# Sheet_1.net
KiCad netlist of a schematic drawn in Altium Designer
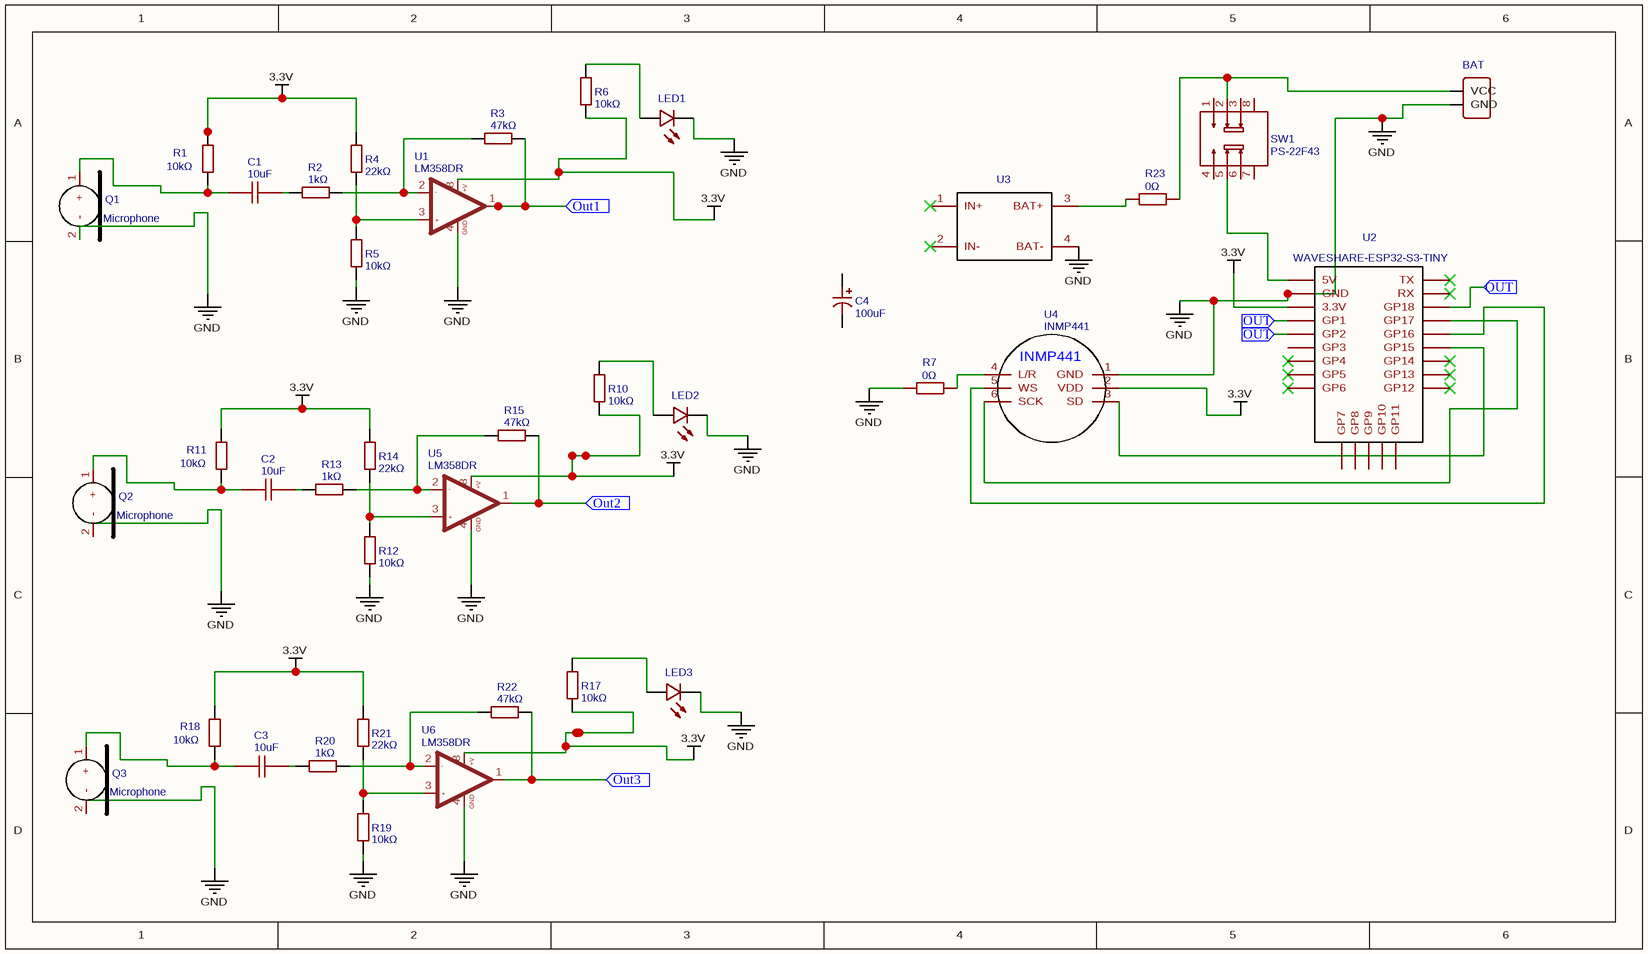
[diagram p0: Sheet_1_.schdoc]

(export (version "E")
  (design (tool "Eeschema 10.0.6"))
  (components
    (comp (ref "BAT")
      (value "HDR-F-2.54_1x2")
      (fields (field (name "CONTRIBUTOR") "LCEDA_Lib"))
      (libsource (lib "altium-import") (part "root_0_HDR-F-2.54_1x2_"))
    )
    (comp (ref "C1")
      (value "10uF")
      (fields
        (field (name "MANUFACTURER PART") "CL21A106KAYNNNE")
        (field (name "MANUFACTURER") "SAMSUNG(三星)")
      )
      (libsource (lib "altium-import") (part "root_0_10uF_"))
    )
    (comp (ref "C2")
      (value "10uF")
      (fields
        (field (name "MANUFACTURER PART") "CL21A106KAYNNNE")
        (field (name "MANUFACTURER") "SAMSUNG(三星)")
      )
      (libsource (lib "altium-import") (part "root_0_10uF_"))
    )
    (comp (ref "C3")
      (value "10uF")
      (fields
        (field (name "MANUFACTURER PART") "CL21A106KAYNNNE")
        (field (name "MANUFACTURER") "SAMSUNG(三星)")
      )
      (libsource (lib "altium-import") (part "root_0_10uF_"))
    )
    (comp (ref "C4")
      (value "100uF")
      (fields
        (field (name "MANUFACTURER") "KNSCHA(科尼盛)")
        (field (name "MANUFACTURER PART") "RVT100UF16V67RV0016")
        (field (name "CONTRIBUTOR") "LCSC")
      )
      (libsource (lib "altium-import") (part "root_3_100uF_"))
    )
    (comp (ref "LED1")
      (value "19-217/BHC-ZL1M2RY/3T")
      (fields (field (name "MANUFACTURER") "EVERLIGHT(亿光)"))
      (libsource (lib "altium-import") (part "root_2_19-217/BHC-ZL1M2RY/3T_"))
    )
    (comp (ref "LED2")
      (value "19-217/BHC-ZL1M2RY/3T")
      (fields (field (name "MANUFACTURER") "EVERLIGHT(亿光)"))
      (libsource (lib "altium-import") (part "root_2_19-217/BHC-ZL1M2RY/3T_"))
    )
    (comp (ref "LED3")
      (value "19-217/BHC-ZL1M2RY/3T")
      (fields (field (name "MANUFACTURER") "EVERLIGHT(亿光)"))
      (libsource (lib "altium-import") (part "root_2_19-217/BHC-ZL1M2RY/3T_"))
    )
    (comp (ref "Q1")
      (value "Microphone")
      (fields (field (name "CONTRIBUTOR") "Мастерская Ленара"))
      (libsource (lib "altium-import") (part "root_0_Microphone_"))
    )
    (comp (ref "Q2")
      (value "Microphone")
      (fields (field (name "CONTRIBUTOR") "Мастерская Ленара"))
      (libsource (lib "altium-import") (part "root_0_Microphone_"))
    )
    (comp (ref "Q3")
      (value "Microphone")
      (fields (field (name "CONTRIBUTOR") "Мастерская Ленара"))
      (libsource (lib "altium-import") (part "root_0_Microphone_"))
    )
    (comp (ref "R1")
      (value "10kΩ")
      (fields (field (name "MANUFACTURER") "YAGEO(国巨)") (field (name "MANUFACTURER PART") "RC0402FR-0710KL"))
      (libsource (lib "altium-import") (part "root_1_10kΩ_"))
    )
    (comp (ref "R2")
      (value "1kΩ")
      (fields
        (field (name "MANUFACTURER") "UNI-ROYAL(厚声)")
        (field (name "MANUFACTURER PART") "0402WGF1001TCE")
      )
      (libsource (lib "altium-import") (part "root_0_1kΩ_"))
    )
    (comp (ref "R3")
      (value "47kΩ")
      (fields
        (field (name "MANUFACTURER") "UNI-ROYAL(厚声)")
        (field (name "MANUFACTURER PART") "0402WGF4702TCE")
      )
      (libsource (lib "altium-import") (part "root_0_47kΩ_"))
    )
    (comp (ref "R4")
      (value "22kΩ")
      (fields
        (field (name "MANUFACTURER") "UNI-ROYAL(厚声)")
        (field (name "MANUFACTURER PART") "0402WGF2202TCE")
      )
      (libsource (lib "altium-import") (part "root_1_22kΩ_"))
    )
    (comp (ref "R5")
      (value "10kΩ")
      (fields (field (name "MANUFACTURER") "YAGEO(国巨)") (field (name "MANUFACTURER PART") "RC0402FR-0710KL"))
      (libsource (lib "altium-import") (part "root_1_10kΩ_"))
    )
    (comp (ref "R6")
      (value "10kΩ")
      (fields (field (name "MANUFACTURER") "YAGEO(国巨)") (field (name "MANUFACTURER PART") "RC0402FR-0710KL"))
      (libsource (lib "altium-import") (part "root_1_10kΩ_"))
    )
    (comp (ref "R7")
      (value "0Ω")
      (fields
        (field (name "MANUFACTURER") "UNI-ROYAL(厚声)")
        (field (name "MANUFACTURER PART") "201007F0000T4E")
        (field (name "CONTRIBUTOR") "LCSC")
      )
      (libsource (lib "altium-import") (part "root_0_0Ω_"))
    )
    (comp (ref "R10")
      (value "10kΩ")
      (fields (field (name "MANUFACTURER") "YAGEO(国巨)") (field (name "MANUFACTURER PART") "RC0402FR-0710KL"))
      (libsource (lib "altium-import") (part "root_1_10kΩ_"))
    )
    (comp (ref "R11")
      (value "10kΩ")
      (fields (field (name "MANUFACTURER") "YAGEO(国巨)") (field (name "MANUFACTURER PART") "RC0402FR-0710KL"))
      (libsource (lib "altium-import") (part "root_1_10kΩ_"))
    )
    (comp (ref "R12")
      (value "10kΩ")
      (fields (field (name "MANUFACTURER") "YAGEO(国巨)") (field (name "MANUFACTURER PART") "RC0402FR-0710KL"))
      (libsource (lib "altium-import") (part "root_1_10kΩ_"))
    )
    (comp (ref "R13")
      (value "1kΩ")
      (fields
        (field (name "MANUFACTURER") "UNI-ROYAL(厚声)")
        (field (name "MANUFACTURER PART") "0402WGF1001TCE")
      )
      (libsource (lib "altium-import") (part "root_0_1kΩ_"))
    )
    (comp (ref "R14")
      (value "22kΩ")
      (fields
        (field (name "MANUFACTURER") "UNI-ROYAL(厚声)")
        (field (name "MANUFACTURER PART") "0402WGF2202TCE")
      )
      (libsource (lib "altium-import") (part "root_1_22kΩ_"))
    )
    (comp (ref "R15")
      (value "47kΩ")
      (fields
        (field (name "MANUFACTURER") "UNI-ROYAL(厚声)")
        (field (name "MANUFACTURER PART") "0402WGF4702TCE")
      )
      (libsource (lib "altium-import") (part "root_0_47kΩ_"))
    )
    (comp (ref "R17")
      (value "10kΩ")
      (fields (field (name "MANUFACTURER") "YAGEO(国巨)") (field (name "MANUFACTURER PART") "RC0402FR-0710KL"))
      (libsource (lib "altium-import") (part "root_1_10kΩ_"))
    )
    (comp (ref "R18")
      (value "10kΩ")
      (fields (field (name "MANUFACTURER") "YAGEO(国巨)") (field (name "MANUFACTURER PART") "RC0402FR-0710KL"))
      (libsource (lib "altium-import") (part "root_1_10kΩ_"))
    )
    (comp (ref "R19")
      (value "10kΩ")
      (fields (field (name "MANUFACTURER") "YAGEO(国巨)") (field (name "MANUFACTURER PART") "RC0402FR-0710KL"))
      (libsource (lib "altium-import") (part "root_1_10kΩ_"))
    )
    (comp (ref "R20")
      (value "1kΩ")
      (fields
        (field (name "MANUFACTURER") "UNI-ROYAL(厚声)")
        (field (name "MANUFACTURER PART") "0402WGF1001TCE")
      )
      (libsource (lib "altium-import") (part "root_0_1kΩ_"))
    )
    (comp (ref "R21")
      (value "22kΩ")
      (fields
        (field (name "MANUFACTURER") "UNI-ROYAL(厚声)")
        (field (name "MANUFACTURER PART") "0402WGF2202TCE")
      )
      (libsource (lib "altium-import") (part "root_1_22kΩ_"))
    )
    (comp (ref "R22")
      (value "47kΩ")
      (fields
        (field (name "MANUFACTURER") "UNI-ROYAL(厚声)")
        (field (name "MANUFACTURER PART") "0402WGF4702TCE")
      )
      (libsource (lib "altium-import") (part "root_0_47kΩ_"))
    )
    (comp (ref "R23")
      (value "0Ω")
      (fields
        (field (name "MANUFACTURER") "UNI-ROYAL(厚声)")
        (field (name "MANUFACTURER PART") "201007F0000T4E")
        (field (name "CONTRIBUTOR") "LCSC")
      )
      (libsource (lib "altium-import") (part "root_0_0Ω_"))
    )
    (comp (ref "SW1")
      (value "PS-22F43")
      (fields (field (name "MANUFACTURER") "G-Switch(品赞)") (field (name "CONTRIBUTOR") "lcsc"))
      (libsource (lib "altium-import") (part "root_0_PS-22F43_"))
    )
    (comp (ref "U1")
      (value "LM358DR")
      (fields (field (name "SUBPART_NO") "1") (field (name "MANUFACTURER") "TI(德州仪器)"))
      (libsource (lib "altium-import") (part "root_0_LM358DR_"))
    )
    (comp (ref "U2")
      (value "WAVESHARE-ESP32-S3-TINY")
      (fields
        (field (name "MANUFACTURER") "WAVESHARE")
        (field (name "MANUFACTURER PART") "ESP32-S3 Mini Development Board")
        (field (name "CONTRIBUTOR") "Mohammed Jerjawi")
      )
      (libsource (lib "altium-import") (part "root_0_WAVESHARE-ESP32-S3-TINY_"))
    )
    (comp (ref "U3")
      (value "Battery Protection  tp4056")
      (fields (field (name "CONTRIBUTOR") "gxgx"))
      (libsource (lib "altium-import") (part "root_0_Battery Protection  tp4056_"))
    )
    (comp (ref "U4")
      (value "INMP441")
      (fields (field (name "MANUFACTURER") "Ali") (field (name "CONTRIBUTOR") "Guest"))
      (libsource (lib "altium-import") (part "root_0_INMP441_"))
    )
    (comp (ref "U5")
      (value "LM358DR")
      (fields (field (name "SUBPART_NO") "1") (field (name "MANUFACTURER") "TI(德州仪器)"))
      (libsource (lib "altium-import") (part "root_0_LM358DR_"))
    )
    (comp (ref "U6")
      (value "LM358DR")
      (fields (field (name "SUBPART_NO") "1") (field (name "MANUFACTURER") "TI(德州仪器)"))
      (libsource (lib "altium-import") (part "root_0_LM358DR_"))
    )
  )
  (nets
    (net (code "1") (name "/OUT") (class "Default")
      (node (ref "U2") (pin "21") (pinfunction "GP18_21") (pintype "passive"))
      (node (ref "U2") (pin "4") (pinfunction "GP1_4") (pintype "passive"))
      (node (ref "U2") (pin "5") (pinfunction "GP2_5") (pintype "passive"))
    )
    (net (code "2") (name "/Out1") (class "Default")
      (node (ref "R3") (pin "2") (pinfunction "2_2") (pintype "passive"))
      (node (ref "U1") (pin "1") (pinfunction "OUT1_1") (pintype "passive"))
    )
    (net (code "3") (name "/Out2") (class "Default")
      (node (ref "R15") (pin "2") (pinfunction "2_2") (pintype "passive"))
      (node (ref "U5") (pin "1") (pinfunction "OUT1_1") (pintype "passive"))
    )
    (net (code "4") (name "/Out3") (class "Default")
      (node (ref "R22") (pin "2") (pinfunction "2_2") (pintype "passive"))
      (node (ref "U6") (pin "1") (pinfunction "OUT1_1") (pintype "passive"))
    )
    (net (code "5") (name "3.3V") (class "Default")
      (node (ref "R1") (pin "2") (pinfunction "2_2") (pintype "passive"))
      (node (ref "R10") (pin "1") (pinfunction "1_1") (pintype "passive"))
      (node (ref "R11") (pin "2") (pinfunction "2_2") (pintype "passive"))
      (node (ref "R14") (pin "2") (pinfunction "2_2") (pintype "passive"))
      (node (ref "R17") (pin "1") (pinfunction "1_1") (pintype "passive"))
      (node (ref "R18") (pin "2") (pinfunction "2_2") (pintype "passive"))
      (node (ref "R21") (pin "2") (pinfunction "2_2") (pintype "passive"))
      (node (ref "R4") (pin "2") (pinfunction "2_2") (pintype "passive"))
      (node (ref "R6") (pin "1") (pinfunction "1_1") (pintype "passive"))
      (node (ref "U1") (pin "8") (pinfunction "+V_8") (pintype "passive"))
      (node (ref "U2") (pin "3") (pinfunction "3.3V_3") (pintype "passive"))
      (node (ref "U4") (pin "2") (pinfunction "VDD_2") (pintype "passive"))
      (node (ref "U5") (pin "8") (pinfunction "+V_8") (pintype "passive"))
      (node (ref "U6") (pin "8") (pinfunction "+V_8") (pintype "passive"))
    )
    (net (code "6") (name "GND") (class "Default")
      (node (ref "BAT") (pin "2") (pinfunction "GND_2") (pintype "passive"))
      (node (ref "LED1") (pin "1") (pinfunction "C_1") (pintype "passive"))
      (node (ref "LED2") (pin "1") (pinfunction "C_1") (pintype "passive"))
      (node (ref "LED3") (pin "1") (pinfunction "C_1") (pintype "passive"))
      (node (ref "Q1") (pin "2") (pinfunction "-_2") (pintype "passive"))
      (node (ref "Q2") (pin "2") (pinfunction "-_2") (pintype "passive"))
      (node (ref "Q3") (pin "2") (pinfunction "-_2") (pintype "passive"))
      (node (ref "R12") (pin "1") (pinfunction "1_1") (pintype "passive"))
      (node (ref "R19") (pin "1") (pinfunction "1_1") (pintype "passive"))
      (node (ref "R5") (pin "1") (pinfunction "1_1") (pintype "passive"))
      (node (ref "R7") (pin "1") (pinfunction "1_1") (pintype "passive"))
      (node (ref "U1") (pin "4") (pinfunction "GND_4") (pintype "passive"))
      (node (ref "U2") (pin "2") (pinfunction "GND_2") (pintype "passive"))
      (node (ref "U3") (pin "4") (pinfunction "BAT-_4") (pintype "passive"))
      (node (ref "U4") (pin "1") (pinfunction "GND_1") (pintype "passive"))
      (node (ref "U5") (pin "4") (pinfunction "GND_4") (pintype "passive"))
      (node (ref "U6") (pin "4") (pinfunction "GND_4") (pintype "passive"))
    )
    (net (code "7") (name "Net-(BAT-VCC)") (class "Default")
      (node (ref "BAT") (pin "1") (pinfunction "VCC_1") (pintype "passive"))
      (node (ref "R23") (pin "2") (pinfunction "2_2") (pintype "passive"))
      (node (ref "SW1") (pin "2") (pinfunction "2_2") (pintype "passive"))
    )
    (net (code "8") (name "Net-(C1-Pad2)") (class "Default")
      (node (ref "C1") (pin "2") (pinfunction "2_2") (pintype "passive"))
      (node (ref "R2") (pin "1") (pinfunction "1_1") (pintype "passive"))
    )
    (net (code "9") (name "Net-(C2-Pad2)") (class "Default")
      (node (ref "C2") (pin "2") (pinfunction "2_2") (pintype "passive"))
      (node (ref "R13") (pin "1") (pinfunction "1_1") (pintype "passive"))
    )
    (net (code "10") (name "Net-(C3-Pad2)") (class "Default")
      (node (ref "C3") (pin "2") (pinfunction "2_2") (pintype "passive"))
      (node (ref "R20") (pin "1") (pinfunction "1_1") (pintype "passive"))
    )
    (net (code "11") (name "Net-(LED1-A)") (class "Default")
      (node (ref "LED1") (pin "2") (pinfunction "A_2") (pintype "passive"))
      (node (ref "R6") (pin "2") (pinfunction "2_2") (pintype "passive"))
    )
    (net (code "12") (name "Net-(LED2-A)") (class "Default")
      (node (ref "LED2") (pin "2") (pinfunction "A_2") (pintype "passive"))
      (node (ref "R10") (pin "2") (pinfunction "2_2") (pintype "passive"))
    )
    (net (code "13") (name "Net-(LED3-A)") (class "Default")
      (node (ref "LED3") (pin "2") (pinfunction "A_2") (pintype "passive"))
      (node (ref "R17") (pin "2") (pinfunction "2_2") (pintype "passive"))
    )
    (net (code "14") (name "Net-(Q1-+)") (class "Default")
      (node (ref "C1") (pin "1") (pinfunction "1_1") (pintype "passive"))
      (node (ref "Q1") (pin "1") (pinfunction "+_1") (pintype "passive"))
      (node (ref "R1") (pin "1") (pinfunction "1_1") (pintype "passive"))
    )
    (net (code "15") (name "Net-(Q2-+)") (class "Default")
      (node (ref "C2") (pin "1") (pinfunction "1_1") (pintype "passive"))
      (node (ref "Q2") (pin "1") (pinfunction "+_1") (pintype "passive"))
      (node (ref "R11") (pin "1") (pinfunction "1_1") (pintype "passive"))
    )
    (net (code "16") (name "Net-(Q3-+)") (class "Default")
      (node (ref "C3") (pin "1") (pinfunction "1_1") (pintype "passive"))
      (node (ref "Q3") (pin "1") (pinfunction "+_1") (pintype "passive"))
      (node (ref "R18") (pin "1") (pinfunction "1_1") (pintype "passive"))
    )
    (net (code "17") (name "Net-(U1-+IN1)") (class "Default")
      (node (ref "R4") (pin "1") (pinfunction "1_1") (pintype "passive"))
      (node (ref "R5") (pin "2") (pinfunction "2_2") (pintype "passive"))
      (node (ref "U1") (pin "3") (pinfunction "+IN1_3") (pintype "passive"))
    )
    (net (code "18") (name "Net-(U1--IN1)") (class "Default")
      (node (ref "R2") (pin "2") (pinfunction "2_2") (pintype "passive"))
      (node (ref "R3") (pin "1") (pinfunction "1_1") (pintype "passive"))
      (node (ref "U1") (pin "2") (pinfunction "-IN1_2") (pintype "passive"))
    )
    (net (code "19") (name "Net-(U2-5V)") (class "Default")
      (node (ref "SW1") (pin "5") (pinfunction "5_5") (pintype "passive"))
      (node (ref "U2") (pin "1") (pinfunction "5V_1") (pintype "passive"))
    )
    (net (code "20") (name "Net-(U2-GP15)") (class "Default")
      (node (ref "U2") (pin "18") (pinfunction "GP15_18") (pintype "passive"))
      (node (ref "U4") (pin "3") (pinfunction "SD_3") (pintype "passive"))
    )
    (net (code "21") (name "Net-(U2-GP16)") (class "Default")
      (node (ref "U2") (pin "19") (pinfunction "GP16_19") (pintype "passive"))
      (node (ref "U4") (pin "5") (pinfunction "WS_5") (pintype "passive"))
    )
    (net (code "22") (name "Net-(U2-GP17)") (class "Default")
      (node (ref "U2") (pin "20") (pinfunction "GP17_20") (pintype "passive"))
      (node (ref "U4") (pin "6") (pinfunction "SCK_6") (pintype "passive"))
    )
    (net (code "23") (name "Net-(U3-BAT+)") (class "Default")
      (node (ref "R23") (pin "1") (pinfunction "1_1") (pintype "passive"))
      (node (ref "U3") (pin "3") (pinfunction "BAT+_3") (pintype "passive"))
    )
    (net (code "24") (name "Net-(U4-L{slash}R)") (class "Default")
      (node (ref "R7") (pin "2") (pinfunction "2_2") (pintype "passive"))
      (node (ref "U4") (pin "4") (pinfunction "L/R_4") (pintype "passive"))
    )
    (net (code "25") (name "Net-(U5-+IN1)") (class "Default")
      (node (ref "R12") (pin "2") (pinfunction "2_2") (pintype "passive"))
      (node (ref "R14") (pin "1") (pinfunction "1_1") (pintype "passive"))
      (node (ref "U5") (pin "3") (pinfunction "+IN1_3") (pintype "passive"))
    )
    (net (code "26") (name "Net-(U5--IN1)") (class "Default")
      (node (ref "R13") (pin "2") (pinfunction "2_2") (pintype "passive"))
      (node (ref "R15") (pin "1") (pinfunction "1_1") (pintype "passive"))
      (node (ref "U5") (pin "2") (pinfunction "-IN1_2") (pintype "passive"))
    )
    (net (code "27") (name "Net-(U6-+IN1)") (class "Default")
      (node (ref "R19") (pin "2") (pinfunction "2_2") (pintype "passive"))
      (node (ref "R21") (pin "1") (pinfunction "1_1") (pintype "passive"))
      (node (ref "U6") (pin "3") (pinfunction "+IN1_3") (pintype "passive"))
    )
    (net (code "28") (name "Net-(U6--IN1)") (class "Default")
      (node (ref "R20") (pin "2") (pinfunction "2_2") (pintype "passive"))
      (node (ref "R22") (pin "1") (pinfunction "1_1") (pintype "passive"))
      (node (ref "U6") (pin "2") (pinfunction "-IN1_2") (pintype "passive"))
    )
    (net (code "29") (name "unconnected-(C4-Pad1)") (class "Default")
      (node (ref "C4") (pin "1") (pinfunction "1_1") (pintype "passive"))
    )
    (net (code "30") (name "unconnected-(C4-Pad2)") (class "Default")
      (node (ref "C4") (pin "2") (pinfunction "2_2") (pintype "passive"))
    )
    (net (code "31") (name "unconnected-(SW1-Pad1)") (class "Default")
      (node (ref "SW1") (pin "1") (pinfunction "1_1") (pintype "passive"))
    )
    (net (code "32") (name "unconnected-(SW1-Pad3)") (class "Default")
      (node (ref "SW1") (pin "3") (pinfunction "3_3") (pintype "passive"))
    )
    (net (code "33") (name "unconnected-(SW1-Pad4)") (class "Default")
      (node (ref "SW1") (pin "4") (pinfunction "4_4") (pintype "passive"))
    )
    (net (code "34") (name "unconnected-(SW1-Pad6)") (class "Default")
      (node (ref "SW1") (pin "6") (pinfunction "6_6") (pintype "passive"))
    )
    (net (code "35") (name "unconnected-(SW1-Pad7)") (class "Default")
      (node (ref "SW1") (pin "7") (pinfunction "7_7") (pintype "passive"))
    )
    (net (code "36") (name "unconnected-(SW1-Pad8)") (class "Default")
      (node (ref "SW1") (pin "8") (pinfunction "8_8") (pintype "passive"))
    )
    (net (code "37") (name "unconnected-(U2-GP3-Pad6)") (class "Default")
      (node (ref "U2") (pin "6") (pinfunction "GP3_6") (pintype "passive"))
    )
    (net (code "38") (name "unconnected-(U2-GP4-Pad7)") (class "Default")
      (node (ref "U2") (pin "7") (pinfunction "GP4_7") (pintype "passive+no_connect"))
    )
    (net (code "39") (name "unconnected-(U2-GP5-Pad8)") (class "Default")
      (node (ref "U2") (pin "8") (pinfunction "GP5_8") (pintype "passive+no_connect"))
    )
    (net (code "40") (name "unconnected-(U2-GP6-Pad9)") (class "Default")
      (node (ref "U2") (pin "9") (pinfunction "GP6_9") (pintype "passive+no_connect"))
    )
    (net (code "41") (name "unconnected-(U2-GP7-Pad10)") (class "Default")
      (node (ref "U2") (pin "10") (pinfunction "GP7_10") (pintype "passive"))
    )
    (net (code "42") (name "unconnected-(U2-GP8-Pad11)") (class "Default")
      (node (ref "U2") (pin "11") (pinfunction "GP8_11") (pintype "passive"))
    )
    (net (code "43") (name "unconnected-(U2-GP9-Pad12)") (class "Default")
      (node (ref "U2") (pin "12") (pinfunction "GP9_12") (pintype "passive"))
    )
    (net (code "44") (name "unconnected-(U2-GP10-Pad13)") (class "Default")
      (node (ref "U2") (pin "13") (pinfunction "GP10_13") (pintype "passive"))
    )
    (net (code "45") (name "unconnected-(U2-GP11-Pad14)") (class "Default")
      (node (ref "U2") (pin "14") (pinfunction "GP11_14") (pintype "passive"))
    )
    (net (code "46") (name "unconnected-(U2-GP12-Pad15)") (class "Default")
      (node (ref "U2") (pin "15") (pinfunction "GP12_15") (pintype "passive+no_connect"))
    )
    (net (code "47") (name "unconnected-(U2-GP13-Pad16)") (class "Default")
      (node (ref "U2") (pin "16") (pinfunction "GP13_16") (pintype "passive+no_connect"))
    )
    (net (code "48") (name "unconnected-(U2-GP14-Pad17)") (class "Default")
      (node (ref "U2") (pin "17") (pinfunction "GP14_17") (pintype "passive+no_connect"))
    )
    (net (code "49") (name "unconnected-(U2-RX-Pad22)") (class "Default")
      (node (ref "U2") (pin "22") (pinfunction "RX_22") (pintype "passive+no_connect"))
    )
    (net (code "50") (name "unconnected-(U2-TX-Pad23)") (class "Default")
      (node (ref "U2") (pin "23") (pinfunction "TX_23") (pintype "passive+no_connect"))
    )
    (net (code "51") (name "unconnected-(U3-IN+-Pad1)") (class "Default")
      (node (ref "U3") (pin "1") (pinfunction "IN+_1") (pintype "passive+no_connect"))
    )
    (net (code "52") (name "unconnected-(U3-IN--Pad2)") (class "Default")
      (node (ref "U3") (pin "2") (pinfunction "IN-_2") (pintype "passive+no_connect"))
    )
  )
)
